# lpf_17_10.net
KiCad netlist of a schematic drawn in Altium Designer
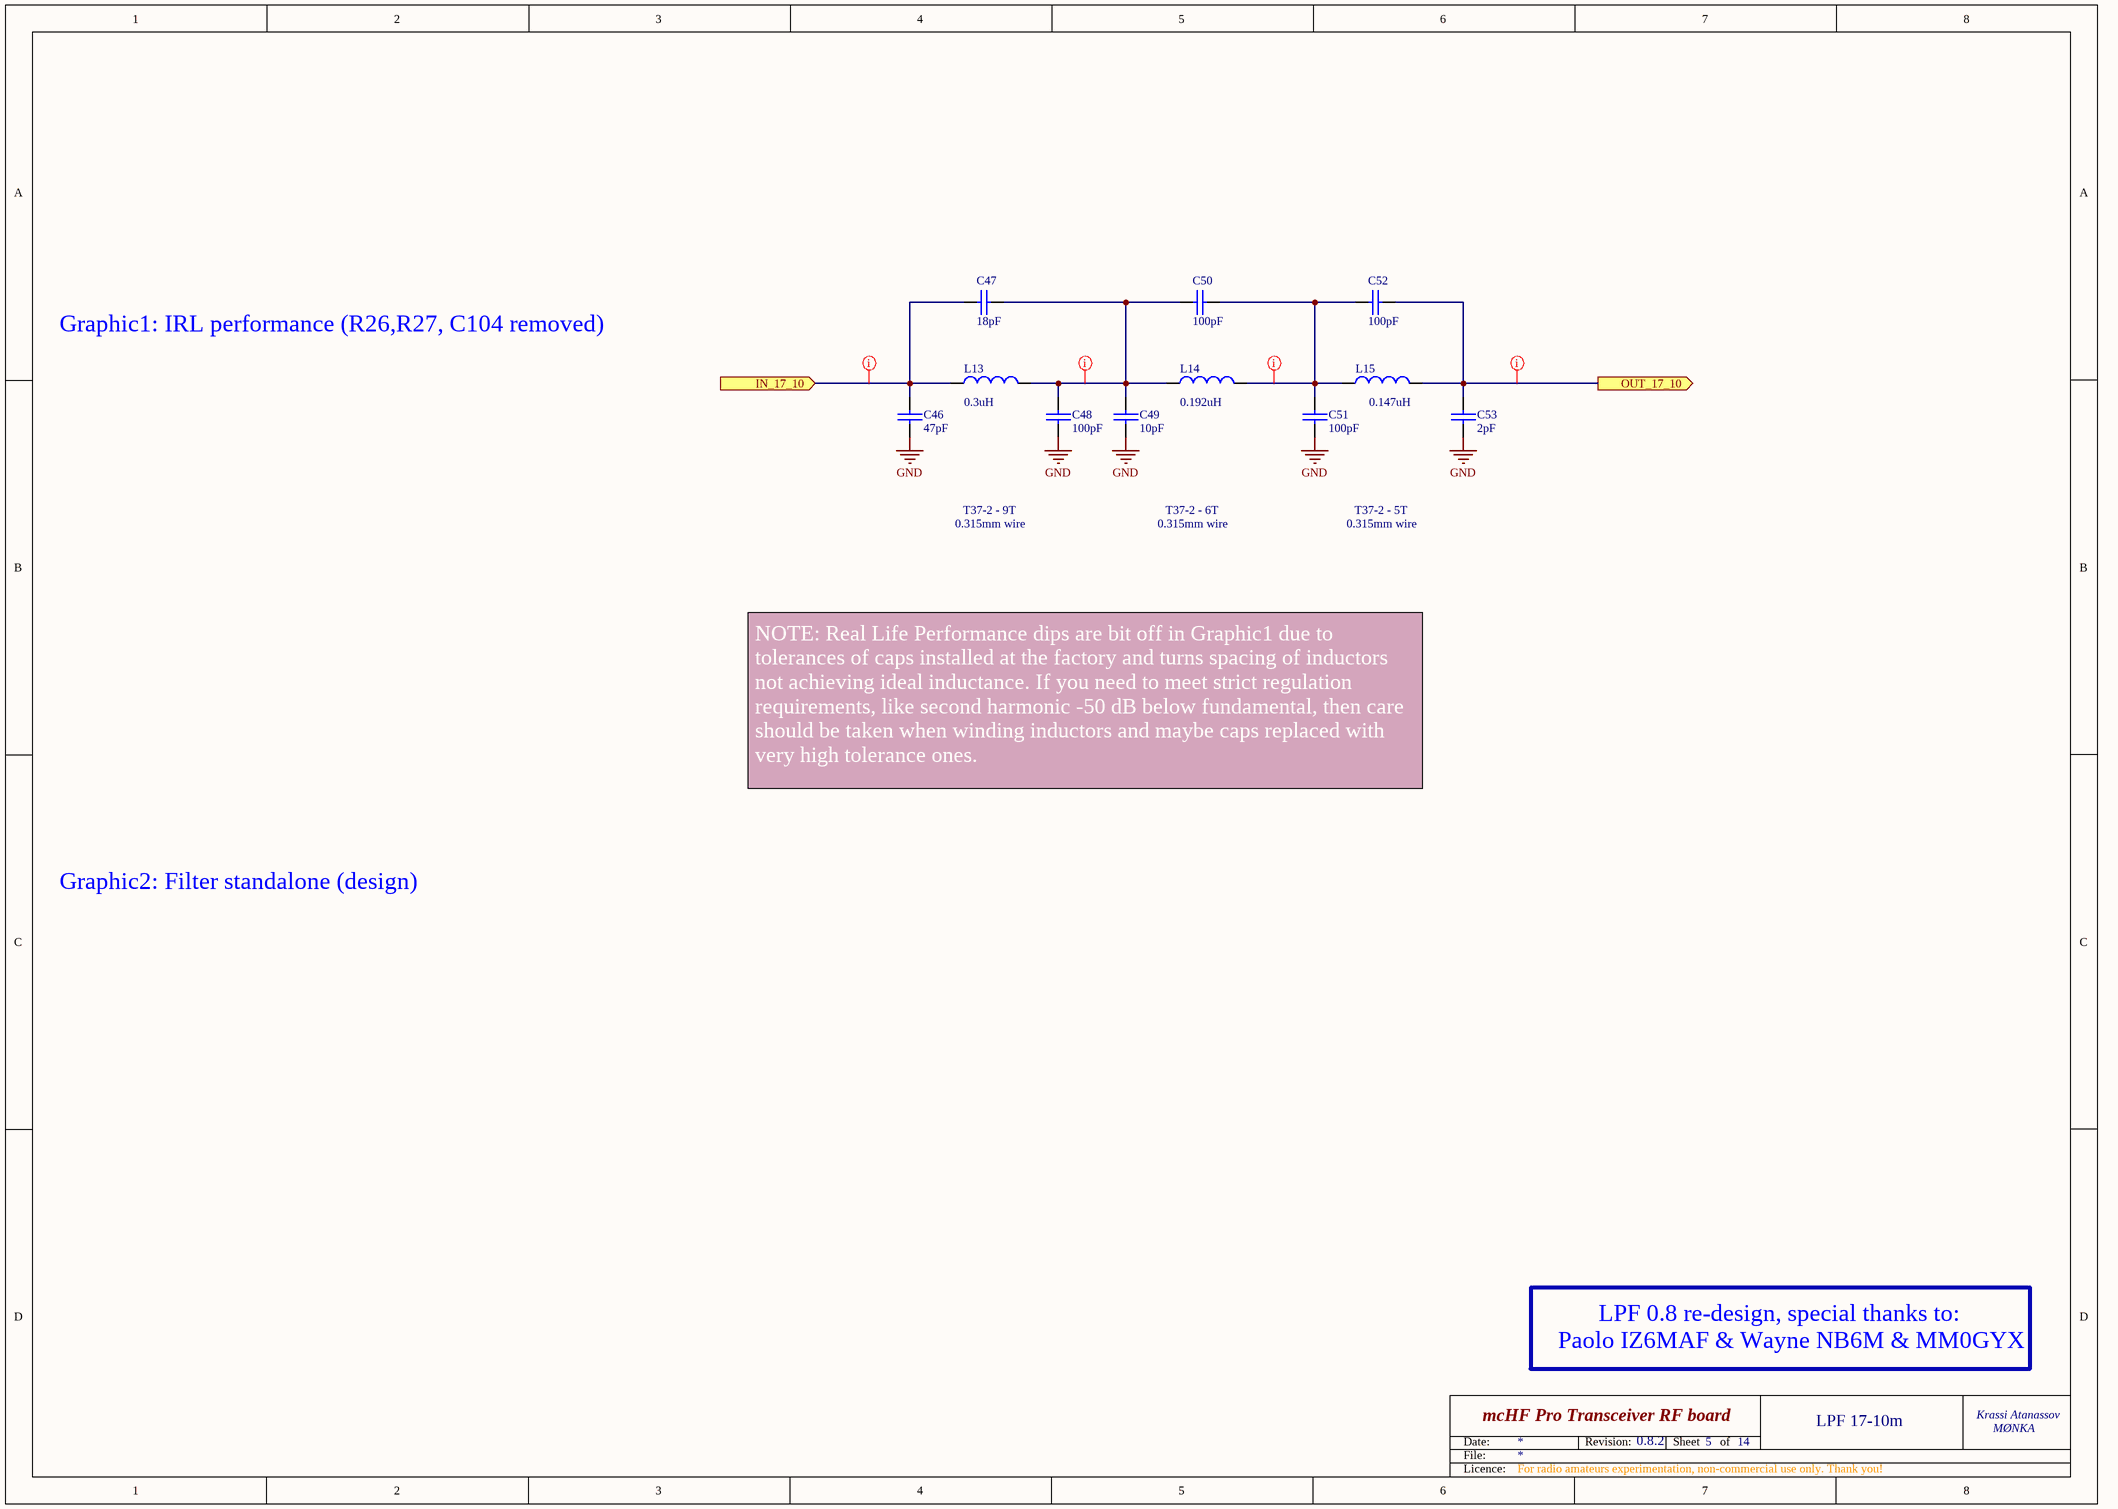
[diagram p0: lpf_17_10.SchDoc]

(export (version "E")
  (design (tool "Eeschema 10.0.6"))
  (components
    (comp (ref "C46")
      (value "47pF")
      (footprint "0805")
      (description "Capacitor")
      (fields (field (name "VOLTAGE") "100V"))
      (libsource (lib "mcHF_rf") (part "CAP"))
    )
    (comp (ref "C47")
      (value "18pF")
      (footprint "0805")
      (description "Capacitor")
      (fields (field (name "VOLTAGE") "100V"))
      (libsource (lib "mcHF_rf") (part "CAP"))
    )
    (comp (ref "C48")
      (value "100pF")
      (footprint "0805")
      (description "Capacitor")
      (fields (field (name "VOLTAGE") "100V"))
      (libsource (lib "mcHF_rf") (part "CAP"))
    )
    (comp (ref "C49")
      (value "10pF")
      (footprint "0805")
      (description "Capacitor")
      (fields (field (name "VOLTAGE") "100V"))
      (libsource (lib "mcHF_rf") (part "CAP"))
    )
    (comp (ref "C50")
      (value "100pF")
      (footprint "0805")
      (description "Capacitor")
      (fields (field (name "VOLTAGE") "100V"))
      (libsource (lib "mcHF_rf") (part "CAP"))
    )
    (comp (ref "C51")
      (value "100pF")
      (footprint "0805")
      (description "Capacitor")
      (fields (field (name "VOLTAGE") "100V"))
      (libsource (lib "mcHF_rf") (part "CAP"))
    )
    (comp (ref "C52")
      (value "100pF")
      (footprint "0805")
      (description "Capacitor")
      (fields (field (name "VOLTAGE") "100V"))
      (libsource (lib "mcHF_rf") (part "CAP"))
    )
    (comp (ref "C53")
      (value "2pF")
      (footprint "0805")
      (description "Capacitor")
      (fields (field (name "VOLTAGE") "100V"))
      (libsource (lib "mcHF_rf") (part "CAP"))
    )
    (comp (ref "L13")
      (value "T37-2")
      (footprint "LPF_IND")
      (description "T37-2 handwound inductor")
      (fields (field (name "INDUCTANCE") "0.3uH"))
      (libsource (lib "mcHF_rf") (part "LPF_IND"))
    )
    (comp (ref "L14")
      (value "T37-2")
      (footprint "LPF_IND")
      (description "T37-2 handwound inductor")
      (fields (field (name "INDUCTANCE") "0.192uH"))
      (libsource (lib "mcHF_rf") (part "LPF_IND"))
    )
    (comp (ref "L15")
      (value "T37-2")
      (footprint "LPF_IND")
      (description "T37-2 handwound inductor")
      (fields (field (name "INDUCTANCE") "0.147uH"))
      (libsource (lib "mcHF_rf") (part "LPF_IND"))
    )
  )
  (nets
    (net (code "1") (name "/IN_17_10") (class "Default")
      (node (ref "C46") (pin "2") (pinfunction "2_2") (pintype "passive"))
      (node (ref "C47") (pin "2") (pinfunction "2_2") (pintype "passive"))
      (node (ref "L13") (pin "1") (pinfunction "1_1") (pintype "passive"))
    )
    (net (code "2") (name "/OUT_17_10") (class "Default")
      (node (ref "C52") (pin "1") (pinfunction "1_1") (pintype "passive"))
      (node (ref "C53") (pin "2") (pinfunction "2_2") (pintype "passive"))
      (node (ref "L15") (pin "2") (pinfunction "2_2") (pintype "passive"))
    )
    (net (code "3") (name "GND") (class "Default")
      (node (ref "C46") (pin "1") (pinfunction "1_1") (pintype "passive"))
      (node (ref "C48") (pin "1") (pinfunction "1_1") (pintype "passive"))
      (node (ref "C49") (pin "1") (pinfunction "1_1") (pintype "passive"))
      (node (ref "C51") (pin "1") (pinfunction "1_1") (pintype "passive"))
      (node (ref "C53") (pin "1") (pinfunction "1_1") (pintype "passive"))
    )
    (net (code "4") (name "Net-(C47-Pad1)") (class "Default")
      (node (ref "C47") (pin "1") (pinfunction "1_1") (pintype "passive"))
      (node (ref "C48") (pin "2") (pinfunction "2_2") (pintype "passive"))
      (node (ref "C49") (pin "2") (pinfunction "2_2") (pintype "passive"))
      (node (ref "C50") (pin "2") (pinfunction "2_2") (pintype "passive"))
      (node (ref "L13") (pin "2") (pinfunction "2_2") (pintype "passive"))
      (node (ref "L14") (pin "1") (pinfunction "1_1") (pintype "passive"))
    )
    (net (code "5") (name "Net-(C50-Pad1)") (class "Default")
      (node (ref "C50") (pin "1") (pinfunction "1_1") (pintype "passive"))
      (node (ref "C51") (pin "2") (pinfunction "2_2") (pintype "passive"))
      (node (ref "C52") (pin "2") (pinfunction "2_2") (pintype "passive"))
      (node (ref "L14") (pin "2") (pinfunction "2_2") (pintype "passive"))
      (node (ref "L15") (pin "1") (pinfunction "1_1") (pintype "passive"))
    )
  )
)
